# Connector_Board.net
KiCad netlist of a schematic drawn in EAGLE
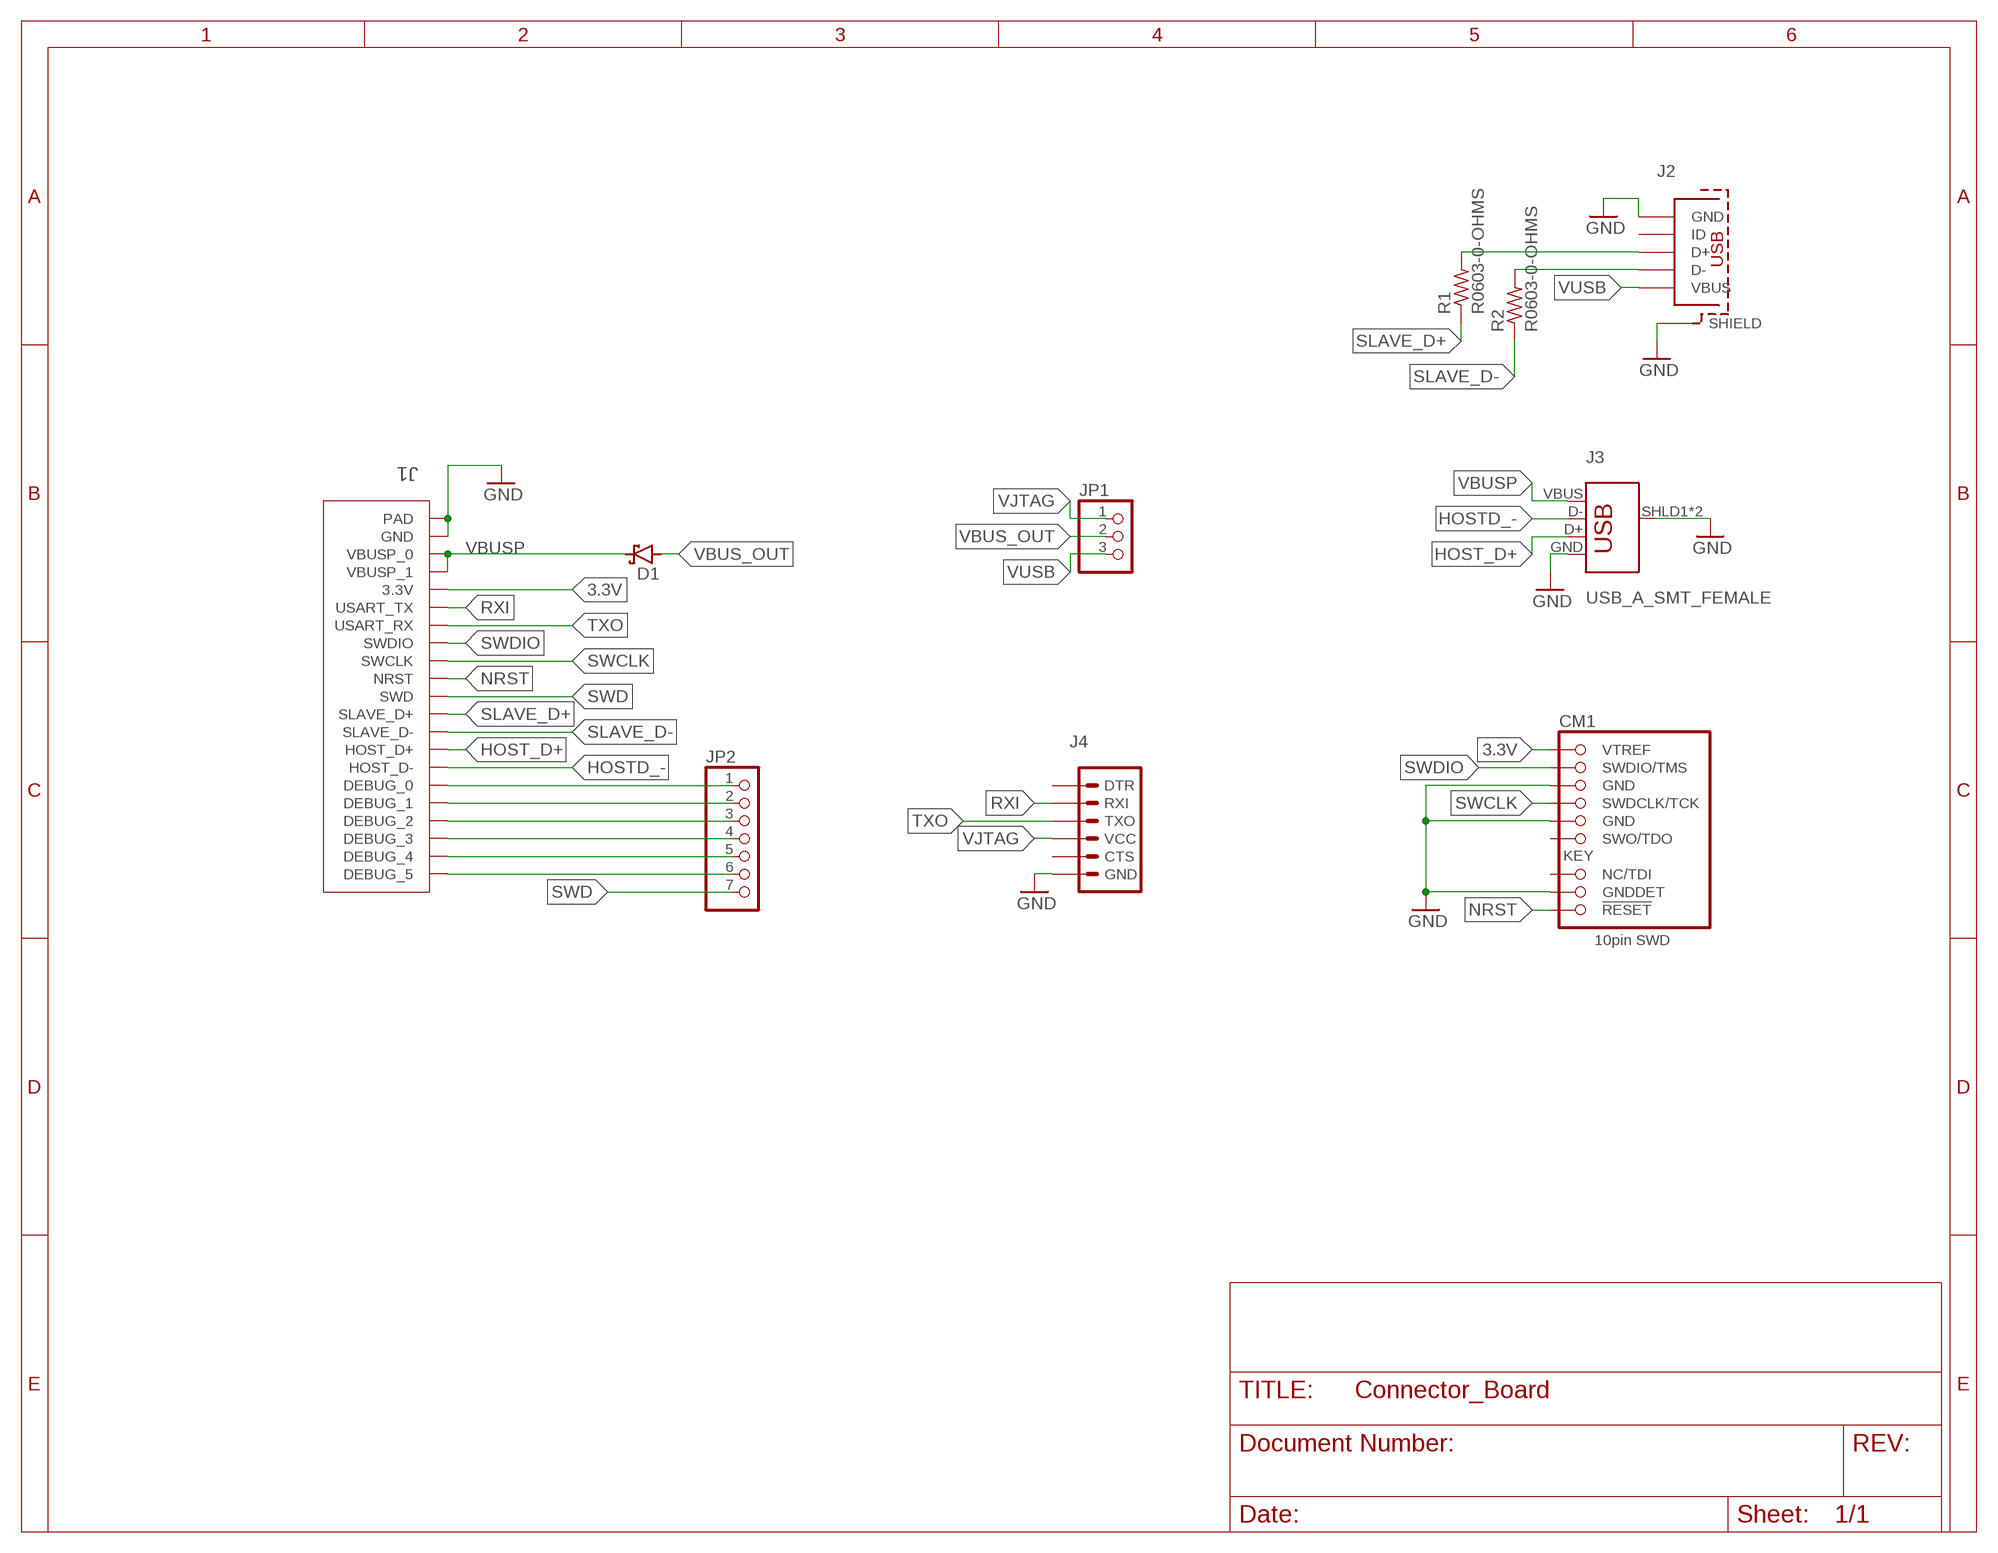
[diagram p0: schematic, sheet 1]

(export (version "E")
  (design (tool "Eeschema 10.0.6"))
  (components
    (comp (ref "CM1")
      (value "FTSH-105-XX-X-DV-K")
      (footprint "eagle-import:CON10_2X5_DUK_FTSH")
      (libsource (lib "eagle-import") (part "FTSH-105-XX-X-DV-K"))
    )
    (comp (ref "D1")
      (value "CDBU0520")
      (footprint "eagle-import:DIOC1709X85N")
      (fields (field (name "MOUSER_PART_NUMBER") "750-CDBU0520") (field (name "RS_PART_NUMBER") "9066848"))
      (libsource (lib "eagle-import") (part "CDBU0520"))
    )
    (comp (ref "J1")
      (value "2-1734592-0")
      (footprint "eagle-import:TE_2-1734592-0")
      (libsource (lib "eagle-import") (part "2-1734592-0"))
    )
    (comp (ref "J2")
      (value "MICRO-USB-SOCKET")
      (footprint "eagle-import:629105136821")
      (libsource (lib "eagle-import") (part "MICRO-USB-SOCKET"))
    )
    (comp (ref "J3")
      (value "USB_A_SMT_FEMALE")
      (footprint "eagle-import:USB-A-S-SILK-FEMALE")
      (libsource (lib "eagle-import") (part "USB_A_SMT_FEMALE"))
    )
    (comp (ref "J4")
      (value "6_PIN_SERIAL_TARGETSILK")
      (footprint "eagle-import:6_PIN_SERIAL_TARGET_SIDE_W_SILK")
      (libsource (lib "eagle-import") (part "6_PIN_SERIAL_TARGETSILK"))
    )
    (comp (ref "JP1")
      (value "PINHD-1X3")
      (footprint "eagle-import:1X03")
      (libsource (lib "eagle-import") (part "PINHD-1X3"))
    )
    (comp (ref "JP2")
      (value "PINHD-1X7")
      (footprint "eagle-import:1X07")
      (libsource (lib "eagle-import") (part "PINHD-1X7"))
    )
    (comp (ref "R1")
      (value "R0603-0-OHMS")
      (footprint "eagle-import:.0603-C-NOSILK")
      (fields
        (field (name "MANUFACTURER_PART_NUMBER") "CRCW06030000Z0EAC")
        (field (name "MOUSER_PART_NUMBER") "71-CRCW06030000Z0EAC")
      )
      (libsource (lib "eagle-import") (part "R0603-0-OHMS"))
    )
    (comp (ref "R2")
      (value "R0603-0-OHMS")
      (footprint "eagle-import:.0603-C-NOSILK")
      (fields
        (field (name "MANUFACTURER_PART_NUMBER") "CRCW06030000Z0EAC")
        (field (name "MOUSER_PART_NUMBER") "71-CRCW06030000Z0EAC")
      )
      (libsource (lib "eagle-import") (part "R0603-0-OHMS"))
    )
  )
  (nets
    (net (code "1") (name "3.3V") (class "Default")
      (node (ref "CM1") (pin "1") (pinfunction "VTREF_1") (pintype "passive"))
      (node (ref "J1") (pin "17") (pinfunction "3.3V_17") (pintype "passive"))
    )
    (net (code "2") (name "GND") (class "Default")
      (node (ref "CM1") (pin "3") (pinfunction "GND_3") (pintype "passive"))
      (node (ref "CM1") (pin "5") (pinfunction "GND_5") (pintype "passive"))
      (node (ref "CM1") (pin "9") (pinfunction "GNDDET_9") (pintype "passive"))
      (node (ref "J1") (pin "20") (pinfunction "GND_20") (pintype "passive"))
      (node (ref "J1") (pin "S1") (pinfunction "PAD_S1") (pintype "bidirectional"))
      (node (ref "J1") (pin "S2") (pinfunction "PAD_S2") (pintype "bidirectional"))
      (node (ref "J2") (pin "5") (pinfunction "GND_5") (pintype "passive"))
      (node (ref "J2") (pin "SHELL") (pinfunction "SHIELD_SHELL") (pintype "passive"))
      (node (ref "J2") (pin "SHELL1") (pinfunction "SHIELD_SHELL1") (pintype "passive"))
      (node (ref "J2") (pin "SHELL2") (pinfunction "SHIELD_SHELL2") (pintype "passive"))
      (node (ref "J2") (pin "SHELL3") (pinfunction "SHIELD_SHELL3") (pintype "passive"))
      (node (ref "J3") (pin "GND") (pinfunction "GND_GND") (pintype "power_in"))
      (node (ref "J3") (pin "SHLD1") (pinfunction "SHIELD_SHLD1") (pintype "bidirectional"))
      (node (ref "J3") (pin "SHLD2") (pinfunction "SHIELD_SHLD2") (pintype "bidirectional"))
      (node (ref "J4") (pin "P$6") (pinfunction "GND_P$6") (pintype "passive"))
    )
    (net (code "3") (name "HOSTD_-") (class "Default")
      (node (ref "J1") (pin "7") (pinfunction "HOST_D-_7") (pintype "passive"))
      (node (ref "J3") (pin "D-") (pinfunction "D-_D-") (pintype "bidirectional"))
    )
    (net (code "4") (name "HOST_D+") (class "Default")
      (node (ref "J1") (pin "8") (pinfunction "HOST_D+_8") (pintype "passive"))
      (node (ref "J3") (pin "D+") (pinfunction "D+_D+") (pintype "bidirectional"))
    )
    (net (code "5") (name "NRST") (class "Default")
      (node (ref "CM1") (pin "10") (pinfunction "~{RESET}_10") (pintype "passive"))
      (node (ref "J1") (pin "12") (pinfunction "NRST_12") (pintype "passive"))
    )
    (net (code "6") (name "Net-(J1-DEBUG_0)") (class "Default")
      (node (ref "J1") (pin "6") (pinfunction "DEBUG_0_6") (pintype "passive"))
      (node (ref "JP2") (pin "1") (pinfunction "1_1") (pintype "passive"))
    )
    (net (code "7") (name "Net-(J1-DEBUG_1)") (class "Default")
      (node (ref "J1") (pin "5") (pinfunction "DEBUG_1_5") (pintype "passive"))
      (node (ref "JP2") (pin "2") (pinfunction "2_2") (pintype "passive"))
    )
    (net (code "8") (name "Net-(J1-DEBUG_2)") (class "Default")
      (node (ref "J1") (pin "4") (pinfunction "DEBUG_2_4") (pintype "passive"))
      (node (ref "JP2") (pin "3") (pinfunction "3_3") (pintype "passive"))
    )
    (net (code "9") (name "Net-(J1-DEBUG_3)") (class "Default")
      (node (ref "J1") (pin "3") (pinfunction "DEBUG_3_3") (pintype "passive"))
      (node (ref "JP2") (pin "4") (pinfunction "4_4") (pintype "passive"))
    )
    (net (code "10") (name "Net-(J1-DEBUG_4)") (class "Default")
      (node (ref "J1") (pin "2") (pinfunction "DEBUG_4_2") (pintype "passive"))
      (node (ref "JP2") (pin "5") (pinfunction "5_5") (pintype "passive"))
    )
    (net (code "11") (name "Net-(J1-DEBUG_5)") (class "Default")
      (node (ref "J1") (pin "1") (pinfunction "DEBUG_5_1") (pintype "passive"))
      (node (ref "JP2") (pin "6") (pinfunction "6_6") (pintype "passive"))
    )
    (net (code "12") (name "Net-(J2-D+)") (class "Default")
      (node (ref "J2") (pin "3") (pinfunction "D+_3") (pintype "passive"))
      (node (ref "R1") (pin "2") (pinfunction "2_2") (pintype "passive"))
    )
    (net (code "13") (name "Net-(J2-D-)") (class "Default")
      (node (ref "J2") (pin "2") (pinfunction "D-_2") (pintype "passive"))
      (node (ref "R2") (pin "2") (pinfunction "2_2") (pintype "passive"))
    )
    (net (code "14") (name "RXI") (class "Default")
      (node (ref "J1") (pin "16") (pinfunction "USART_TX_16") (pintype "passive"))
      (node (ref "J4") (pin "P$3") (pinfunction "RXI_P$3") (pintype "passive"))
    )
    (net (code "15") (name "SLAVE_D+") (class "Default")
      (node (ref "J1") (pin "10") (pinfunction "SLAVE_D+_10") (pintype "passive"))
      (node (ref "R1") (pin "1") (pinfunction "1_1") (pintype "passive"))
    )
    (net (code "16") (name "SLAVE_D-") (class "Default")
      (node (ref "J1") (pin "9") (pinfunction "SLAVE_D-_9") (pintype "passive"))
      (node (ref "R2") (pin "1") (pinfunction "1_1") (pintype "passive"))
    )
    (net (code "17") (name "SWCLK") (class "Default")
      (node (ref "CM1") (pin "4") (pinfunction "SWDCLK/TCK_4") (pintype "passive"))
      (node (ref "J1") (pin "13") (pinfunction "SWCLK_13") (pintype "passive"))
    )
    (net (code "18") (name "SWD") (class "Default")
      (node (ref "J1") (pin "11") (pinfunction "SWD_11") (pintype "passive"))
      (node (ref "JP2") (pin "7") (pinfunction "7_7") (pintype "passive"))
    )
    (net (code "19") (name "SWDIO") (class "Default")
      (node (ref "CM1") (pin "2") (pinfunction "SWDIO/TMS_2") (pintype "passive"))
      (node (ref "J1") (pin "14") (pinfunction "SWDIO_14") (pintype "passive"))
    )
    (net (code "20") (name "TXO") (class "Default")
      (node (ref "J1") (pin "15") (pinfunction "USART_RX_15") (pintype "passive"))
      (node (ref "J4") (pin "P$2") (pinfunction "TXO_P$2") (pintype "passive"))
    )
    (net (code "21") (name "VBUSP") (class "Default")
      (node (ref "D1") (pin "1") (pinfunction "C_1") (pintype "passive"))
      (node (ref "J1") (pin "18") (pinfunction "VBUSP_1_18") (pintype "passive"))
      (node (ref "J1") (pin "19") (pinfunction "VBUSP_0_19") (pintype "passive"))
      (node (ref "J3") (pin "VBUS") (pinfunction "VBUS_VBUS") (pintype "power_in"))
    )
    (net (code "22") (name "VBUS_OUT") (class "Default")
      (node (ref "D1") (pin "2") (pinfunction "A_2") (pintype "passive"))
      (node (ref "JP1") (pin "2") (pinfunction "2_2") (pintype "passive"))
    )
    (net (code "23") (name "VJTAG") (class "Default")
      (node (ref "J4") (pin "P$4") (pinfunction "VCC_P$4") (pintype "passive"))
      (node (ref "JP1") (pin "1") (pinfunction "1_1") (pintype "passive"))
    )
    (net (code "24") (name "VUSB") (class "Default")
      (node (ref "J2") (pin "1") (pinfunction "VBUS_1") (pintype "passive"))
      (node (ref "JP1") (pin "3") (pinfunction "3_3") (pintype "passive"))
    )
    (net (code "25") (name "unconnected-(CM1-NC{slash}TDI-Pad8)") (class "Default")
      (node (ref "CM1") (pin "8") (pinfunction "NC/TDI_8") (pintype "passive"))
    )
    (net (code "26") (name "unconnected-(CM1-SWO{slash}TDO-Pad6)") (class "Default")
      (node (ref "CM1") (pin "6") (pinfunction "SWO/TDO_6") (pintype "passive"))
    )
    (net (code "27") (name "unconnected-(J2-ID-Pad4)") (class "Default")
      (node (ref "J2") (pin "4") (pinfunction "ID_4") (pintype "passive"))
    )
    (net (code "28") (name "unconnected-(J4-CTS-PadP$5)") (class "Default")
      (node (ref "J4") (pin "P$5") (pinfunction "CTS_P$5") (pintype "passive"))
    )
    (net (code "29") (name "unconnected-(J4-DTR-PadP$1)") (class "Default")
      (node (ref "J4") (pin "P$1") (pinfunction "DTR_P$1") (pintype "passive"))
    )
  )
)
